# TPA_MONO.net
KiCad netlist of a schematic drawn in Altium Designer
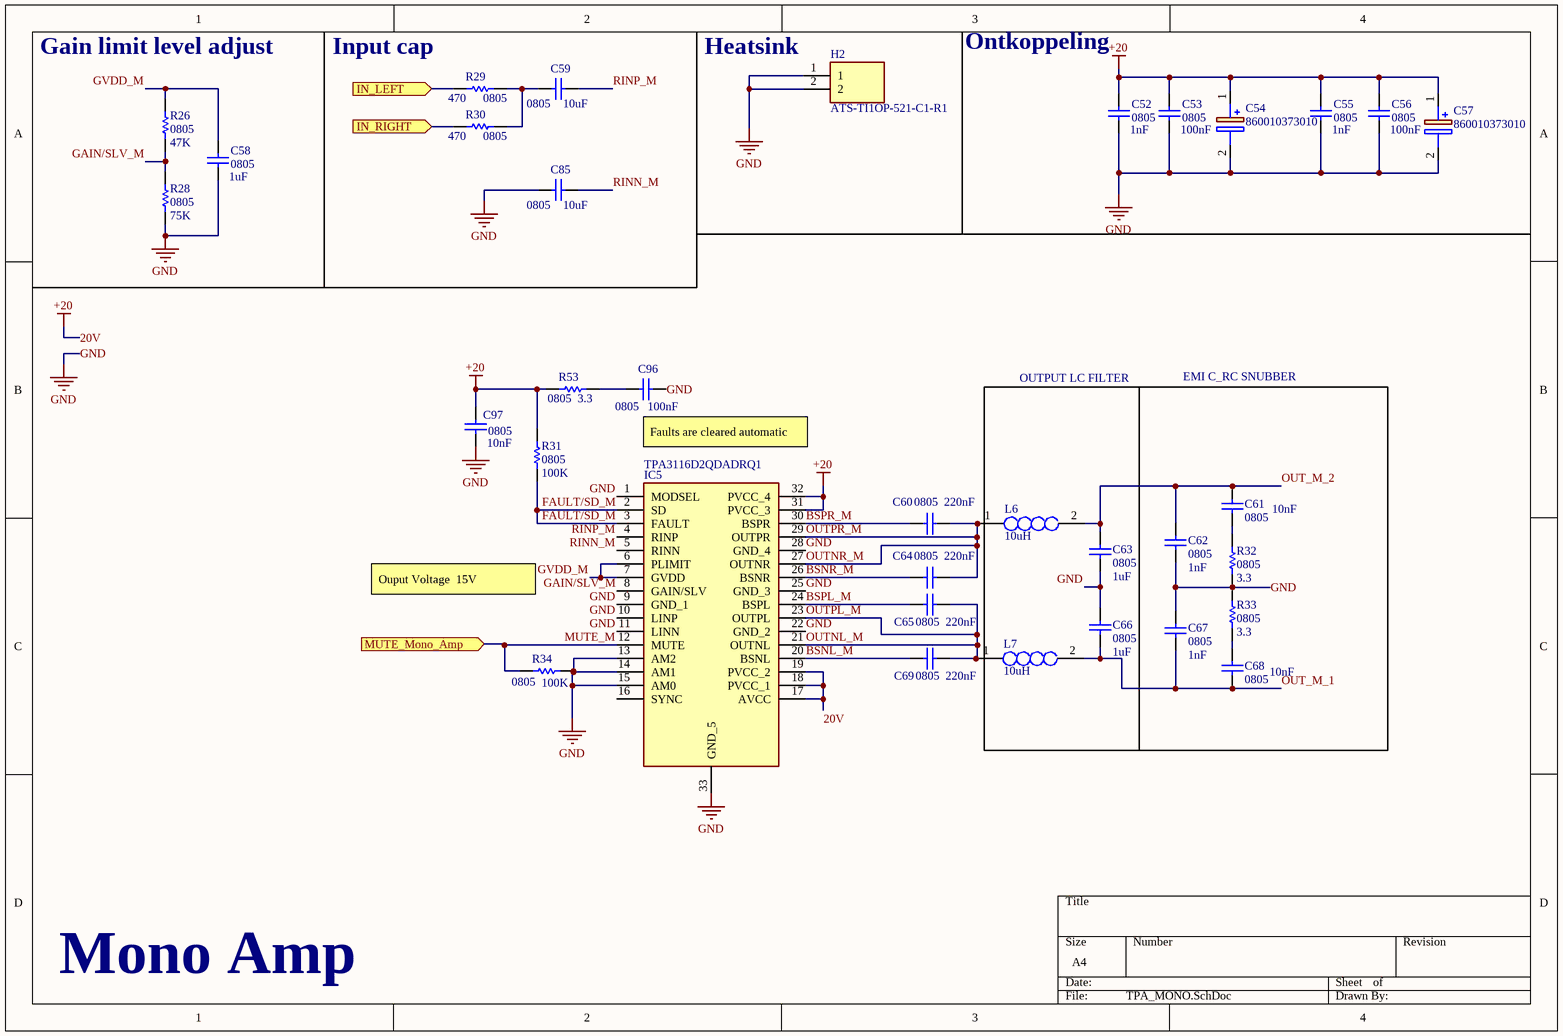
[diagram p0: TPA_MONO.SchDoc]

(export (version "E")
  (design (tool "Eeschema 10.0.6"))
  (components
    (comp (ref "C52")
      (value "0805")
      (footprint "6-0805_N")
      (description "Capacitor")
      (fields (field (name "ALTIUM_VALUE") "1nF") (field (name "PUBLISHER") "Altium Limited"))
      (libsource (lib "Miscellaneous Devices") (part "Cap"))
    )
    (comp (ref "C53")
      (value "0805")
      (footprint "6-0805_N")
      (description "Capacitor")
      (fields (field (name "ALTIUM_VALUE") "100nF") (field (name "PUBLISHER") "Altium Limited"))
      (libsource (lib "Miscellaneous Devices") (part "Cap"))
    )
    (comp (ref "C54")
      (value "860010373010")
      (footprint "SamacSys:CAPPRD250W52D630H1250")
      (description "Capacitor Polarised")
      (fields (field (name "MOUSER PART NUMBER") "710-860010373010"))
      (libsource (lib "*") (part "860010373010"))
    )
    (comp (ref "C55")
      (value "0805")
      (footprint "6-0805_N")
      (description "Capacitor")
      (fields (field (name "ALTIUM_VALUE") "1nF") (field (name "PUBLISHER") "Altium Limited"))
      (libsource (lib "Miscellaneous Devices") (part "Cap"))
    )
    (comp (ref "C56")
      (value "0805")
      (footprint "6-0805_N")
      (description "Capacitor")
      (fields (field (name "ALTIUM_VALUE") "100nF") (field (name "PUBLISHER") "Altium Limited"))
      (libsource (lib "Miscellaneous Devices") (part "Cap"))
    )
    (comp (ref "C57")
      (value "860010373010")
      (footprint "SamacSys:CAPPRD250W52D630H1250")
      (description "Capacitor Polarised")
      (fields (field (name "MOUSER PART NUMBER") "710-860010373010"))
      (libsource (lib "*") (part "860010373010"))
    )
    (comp (ref "C58")
      (value "0805")
      (footprint "6-0805_N")
      (description "Capacitor")
      (fields (field (name "ALTIUM_VALUE") "1uF") (field (name "PUBLISHER") "Altium Limited"))
      (libsource (lib "Miscellaneous Devices") (part "Cap"))
    )
    (comp (ref "C59")
      (value "0805")
      (footprint "6-0805_N")
      (description "Capacitor")
      (fields (field (name "ALTIUM_VALUE") "10uF") (field (name "PUBLISHER") "Altium Limited"))
      (libsource (lib "Miscellaneous Devices") (part "Cap"))
    )
    (comp (ref "C60")
      (value "0805")
      (footprint "6-0805_N")
      (description "Capacitor")
      (fields (field (name "ALTIUM_VALUE") "220nF") (field (name "PUBLISHER") "Altium Limited"))
      (libsource (lib "Miscellaneous Devices") (part "Cap"))
    )
    (comp (ref "C61")
      (value "0805")
      (footprint "6-0805_N")
      (description "Capacitor")
      (fields (field (name "ALTIUM_VALUE") "10nF") (field (name "PUBLISHER") "Altium Limited"))
      (libsource (lib "Miscellaneous Devices") (part "Cap"))
    )
    (comp (ref "C62")
      (value "0805")
      (footprint "6-0805_N")
      (description "Capacitor")
      (fields (field (name "ALTIUM_VALUE") "1nF") (field (name "PUBLISHER") "Altium Limited"))
      (libsource (lib "Miscellaneous Devices") (part "Cap"))
    )
    (comp (ref "C63")
      (value "0805")
      (footprint "6-0805_N")
      (description "Capacitor")
      (fields (field (name "ALTIUM_VALUE") "1uF") (field (name "PUBLISHER") "Altium Limited"))
      (libsource (lib "Miscellaneous Devices") (part "Cap"))
    )
    (comp (ref "C64")
      (value "0805")
      (footprint "6-0805_N")
      (description "Capacitor")
      (fields (field (name "ALTIUM_VALUE") "220nF") (field (name "PUBLISHER") "Altium Limited"))
      (libsource (lib "Miscellaneous Devices") (part "Cap"))
    )
    (comp (ref "C65")
      (value "0805")
      (footprint "6-0805_N")
      (description "Capacitor")
      (fields (field (name "ALTIUM_VALUE") "220nF") (field (name "PUBLISHER") "Altium Limited"))
      (libsource (lib "Miscellaneous Devices") (part "Cap"))
    )
    (comp (ref "C66")
      (value "0805")
      (footprint "6-0805_N")
      (description "Capacitor")
      (fields (field (name "ALTIUM_VALUE") "1uF") (field (name "PUBLISHER") "Altium Limited"))
      (libsource (lib "Miscellaneous Devices") (part "Cap"))
    )
    (comp (ref "C67")
      (value "0805")
      (footprint "6-0805_N")
      (description "Capacitor")
      (fields (field (name "ALTIUM_VALUE") "1nF") (field (name "PUBLISHER") "Altium Limited"))
      (libsource (lib "Miscellaneous Devices") (part "Cap"))
    )
    (comp (ref "C68")
      (value "0805")
      (footprint "6-0805_N")
      (description "Capacitor")
      (fields (field (name "ALTIUM_VALUE") "10nF") (field (name "PUBLISHER") "Altium Limited"))
      (libsource (lib "Miscellaneous Devices") (part "Cap"))
    )
    (comp (ref "C69")
      (value "0805")
      (footprint "6-0805_N")
      (description "Capacitor")
      (fields (field (name "ALTIUM_VALUE") "220nF") (field (name "PUBLISHER") "Altium Limited"))
      (libsource (lib "Miscellaneous Devices") (part "Cap"))
    )
    (comp (ref "C85")
      (value "0805")
      (footprint "6-0805_N")
      (description "Capacitor")
      (fields (field (name "ALTIUM_VALUE") "10uF") (field (name "PUBLISHER") "Altium Limited"))
      (libsource (lib "Miscellaneous Devices") (part "Cap"))
    )
    (comp (ref "C96")
      (value "0805")
      (footprint "6-0805_N")
      (description "Capacitor")
      (fields (field (name "ALTIUM_VALUE") "100nF") (field (name "PUBLISHER") "Altium Limited"))
      (libsource (lib "Miscellaneous Devices") (part "Cap"))
    )
    (comp (ref "C97")
      (value "0805")
      (footprint "6-0805_N")
      (description "Capacitor")
      (fields (field (name "ALTIUM_VALUE") "10nF") (field (name "PUBLISHER") "Altium Limited"))
      (libsource (lib "Miscellaneous Devices") (part "Cap"))
    )
    (comp (ref "H2")
      (value "ATS-TI1OP-521-C1-R1")
      (footprint "SamacSys:ATSTI1OP521C1R1")
      (description "Hardware")
      (fields (field (name "MOUSER PART NUMBER") "984-ATS-TI1OP521C1R1"))
      (libsource (lib "SamacSys") (part "ATS-TI1OP-521-C1-R1"))
    )
    (comp (ref "IC5")
      (value "TPA3116D2QDADRQ1")
      (footprint "SamacSys:SOP65P810X120-33N")
      (description "Integrated Circuit")
      (fields (field (name "MOUSER PART NUMBER") "595-TPA3116D2QDADRQ1"))
      (libsource (lib "SamacSys") (part "TPA3116D2QDADRQ1"))
    )
    (comp (ref "L6")
      (value "10uH")
      (footprint "SamacSys:INDPM110100X400N")
      (description "Inductor")
      (fields
        (field (name "MANUFACTURER_PART_NUMBER") "SRP1038A-4R7M")
        (field (name "MOUSER PART NUMBER") "652-SRP1038A-4R7M")
      )
      (libsource (lib "*") (part "SRP1038A-4R7M"))
    )
    (comp (ref "L7")
      (value "10uH")
      (footprint "SamacSys:INDPM110100X400N")
      (description "Inductor")
      (fields
        (field (name "MANUFACTURER_PART_NUMBER") "SRP1038A-4R7M")
        (field (name "MOUSER PART NUMBER") "652-SRP1038A-4R7M")
      )
      (libsource (lib "*") (part "SRP1038A-4R7M"))
    )
    (comp (ref "R26")
      (value "0805")
      (footprint "6-0805_N")
      (description "Resistor")
      (fields (field (name "ALTIUM_VALUE") "47K") (field (name "PUBLISHER") "Altium Limited"))
      (libsource (lib "Miscellaneous Devices") (part "Res1"))
    )
    (comp (ref "R28")
      (value "0805")
      (footprint "6-0805_N")
      (description "Resistor")
      (fields (field (name "ALTIUM_VALUE") "75K") (field (name "PUBLISHER") "Altium Limited"))
      (libsource (lib "Miscellaneous Devices") (part "Res1"))
    )
    (comp (ref "R29")
      (value "0805")
      (footprint "6-0805_N")
      (description "Resistor")
      (fields (field (name "ALTIUM_VALUE") "470") (field (name "PUBLISHER") "Altium Limited"))
      (libsource (lib "Miscellaneous Devices") (part "Res1"))
    )
    (comp (ref "R30")
      (value "0805")
      (footprint "6-0805_N")
      (description "Resistor")
      (fields (field (name "ALTIUM_VALUE") "470") (field (name "PUBLISHER") "Altium Limited"))
      (libsource (lib "Miscellaneous Devices") (part "Res1"))
    )
    (comp (ref "R31")
      (value "0805")
      (footprint "6-0805_N")
      (description "Resistor")
      (fields (field (name "ALTIUM_VALUE") "100K") (field (name "PUBLISHER") "Altium Limited"))
      (libsource (lib "Miscellaneous Devices") (part "Res1"))
    )
    (comp (ref "R32")
      (value "0805")
      (footprint "6-0805_N")
      (description "Resistor")
      (fields (field (name "ALTIUM_VALUE") "3.3") (field (name "PUBLISHER") "Altium Limited"))
      (libsource (lib "Miscellaneous Devices") (part "Res1"))
    )
    (comp (ref "R33")
      (value "0805")
      (footprint "6-0805_N")
      (description "Resistor")
      (fields (field (name "ALTIUM_VALUE") "3.3") (field (name "PUBLISHER") "Altium Limited"))
      (libsource (lib "Miscellaneous Devices") (part "Res1"))
    )
    (comp (ref "R34")
      (value "0805")
      (footprint "6-0805_N")
      (description "Resistor")
      (fields (field (name "ALTIUM_VALUE") "100K") (field (name "PUBLISHER") "Altium Limited"))
      (libsource (lib "Miscellaneous Devices") (part "Res1"))
    )
    (comp (ref "R53")
      (value "0805")
      (footprint "6-0805_N")
      (description "Resistor")
      (fields (field (name "ALTIUM_VALUE") "3.3") (field (name "PUBLISHER") "Altium Limited"))
      (libsource (lib "Miscellaneous Devices") (part "Res1"))
    )
  )
  (nets
    (net (code "1") (name "+20") (class "Default")
      (node (ref "C52") (pin "1") (pinfunction "1_1") (pintype "passive"))
      (node (ref "C53") (pin "1") (pinfunction "1_1") (pintype "passive"))
      (node (ref "C54") (pin "1") (pinfunction "+_1") (pintype "passive"))
      (node (ref "C55") (pin "1") (pinfunction "1_1") (pintype "passive"))
      (node (ref "C56") (pin "1") (pinfunction "1_1") (pintype "passive"))
      (node (ref "C57") (pin "1") (pinfunction "+_1") (pintype "passive"))
      (node (ref "C97") (pin "1") (pinfunction "1_1") (pintype "passive"))
      (node (ref "IC5") (pin "17") (pinfunction "AVCC_17") (pintype "passive"))
      (node (ref "IC5") (pin "18") (pinfunction "PVCC_1_18") (pintype "passive"))
      (node (ref "IC5") (pin "19") (pinfunction "PVCC_2_19") (pintype "passive"))
      (node (ref "IC5") (pin "31") (pinfunction "PVCC_3_31") (pintype "passive"))
      (node (ref "IC5") (pin "32") (pinfunction "PVCC_4_32") (pintype "passive"))
      (node (ref "R31") (pin "2") (pinfunction "2_2") (pintype "passive"))
      (node (ref "R53") (pin "2") (pinfunction "2_2") (pintype "passive"))
    )
    (net (code "2") (name "/BSNL_M") (class "Default")
      (node (ref "C69") (pin "1") (pinfunction "1_1") (pintype "passive"))
      (node (ref "IC5") (pin "20") (pinfunction "BSNL_20") (pintype "passive"))
    )
    (net (code "3") (name "/BSNR_M") (class "Default")
      (node (ref "C64") (pin "1") (pinfunction "1_1") (pintype "passive"))
      (node (ref "IC5") (pin "26") (pinfunction "BSNR_26") (pintype "passive"))
    )
    (net (code "4") (name "/BSPL_M") (class "Default")
      (node (ref "C65") (pin "1") (pinfunction "1_1") (pintype "passive"))
      (node (ref "IC5") (pin "24") (pinfunction "BSPL_24") (pintype "passive"))
    )
    (net (code "5") (name "/BSPR_M") (class "Default")
      (node (ref "C60") (pin "1") (pinfunction "1_1") (pintype "passive"))
      (node (ref "IC5") (pin "30") (pinfunction "BSPR_30") (pintype "passive"))
    )
    (net (code "6") (name "/FAULT{slash}SD_M") (class "Default")
      (node (ref "IC5") (pin "2") (pinfunction "SD_2") (pintype "passive"))
      (node (ref "IC5") (pin "3") (pinfunction "FAULT_3") (pintype "passive"))
      (node (ref "R31") (pin "1") (pinfunction "1_1") (pintype "passive"))
    )
    (net (code "7") (name "/GAIN{slash}SLV_M") (class "Default")
      (node (ref "IC5") (pin "8") (pinfunction "GAIN/SLV_8") (pintype "passive"))
      (node (ref "R26") (pin "1") (pinfunction "1_1") (pintype "passive"))
      (node (ref "R28") (pin "2") (pinfunction "2_2") (pintype "passive"))
    )
    (net (code "8") (name "/GVDD_M") (class "Default")
      (node (ref "C58") (pin "1") (pinfunction "1_1") (pintype "passive"))
      (node (ref "IC5") (pin "6") (pinfunction "PLIMIT_6") (pintype "passive"))
      (node (ref "IC5") (pin "7") (pinfunction "GVDD_7") (pintype "passive"))
      (node (ref "R26") (pin "2") (pinfunction "2_2") (pintype "passive"))
    )
    (net (code "9") (name "/IN_LEFT") (class "Default")
      (node (ref "R29") (pin "2") (pinfunction "2_2") (pintype "passive"))
    )
    (net (code "10") (name "/IN_RIGHT") (class "Default")
      (node (ref "R30") (pin "2") (pinfunction "2_2") (pintype "passive"))
    )
    (net (code "11") (name "/MUTE_M") (class "Default")
      (node (ref "IC5") (pin "12") (pinfunction "MUTE_12") (pintype "passive"))
      (node (ref "R34") (pin "2") (pinfunction "2_2") (pintype "passive"))
    )
    (net (code "12") (name "/OUTNL_M") (class "Default")
      (node (ref "C65") (pin "2") (pinfunction "2_2") (pintype "passive"))
      (node (ref "C69") (pin "2") (pinfunction "2_2") (pintype "passive"))
      (node (ref "IC5") (pin "21") (pinfunction "OUTNL_21") (pintype "passive"))
      (node (ref "IC5") (pin "23") (pinfunction "OUTPL_23") (pintype "passive"))
      (node (ref "L7") (pin "1") (pinfunction "1_1") (pintype "passive"))
    )
    (net (code "13") (name "/OUTNR_M") (class "Default")
      (node (ref "C60") (pin "2") (pinfunction "2_2") (pintype "passive"))
      (node (ref "C64") (pin "2") (pinfunction "2_2") (pintype "passive"))
      (node (ref "IC5") (pin "27") (pinfunction "OUTNR_27") (pintype "passive"))
      (node (ref "IC5") (pin "29") (pinfunction "OUTPR_29") (pintype "passive"))
      (node (ref "L6") (pin "1") (pinfunction "1_1") (pintype "passive"))
    )
    (net (code "14") (name "/OUT_M_1") (class "Default")
      (node (ref "C66") (pin "1") (pinfunction "1_1") (pintype "passive"))
      (node (ref "C67") (pin "1") (pinfunction "1_1") (pintype "passive"))
      (node (ref "C68") (pin "1") (pinfunction "1_1") (pintype "passive"))
      (node (ref "L7") (pin "2") (pinfunction "2_2") (pintype "passive"))
    )
    (net (code "15") (name "/OUT_M_2") (class "Default")
      (node (ref "C61") (pin "2") (pinfunction "2_2") (pintype "passive"))
      (node (ref "C62") (pin "2") (pinfunction "2_2") (pintype "passive"))
      (node (ref "C63") (pin "2") (pinfunction "2_2") (pintype "passive"))
      (node (ref "L6") (pin "2") (pinfunction "2_2") (pintype "passive"))
    )
    (net (code "16") (name "/RINN_M") (class "Default")
      (node (ref "C85") (pin "2") (pinfunction "2_2") (pintype "passive"))
      (node (ref "IC5") (pin "5") (pinfunction "RINN_5") (pintype "passive"))
    )
    (net (code "17") (name "/RINP_M") (class "Default")
      (node (ref "C59") (pin "2") (pinfunction "2_2") (pintype "passive"))
      (node (ref "IC5") (pin "4") (pinfunction "RINP_4") (pintype "passive"))
    )
    (net (code "18") (name "GND") (class "Default")
      (node (ref "C52") (pin "2") (pinfunction "2_2") (pintype "passive"))
      (node (ref "C53") (pin "2") (pinfunction "2_2") (pintype "passive"))
      (node (ref "C54") (pin "2") (pinfunction "-_2") (pintype "passive"))
      (node (ref "C55") (pin "2") (pinfunction "2_2") (pintype "passive"))
      (node (ref "C56") (pin "2") (pinfunction "2_2") (pintype "passive"))
      (node (ref "C57") (pin "2") (pinfunction "-_2") (pintype "passive"))
      (node (ref "C58") (pin "2") (pinfunction "2_2") (pintype "passive"))
      (node (ref "C62") (pin "1") (pinfunction "1_1") (pintype "passive"))
      (node (ref "C63") (pin "1") (pinfunction "1_1") (pintype "passive"))
      (node (ref "C66") (pin "2") (pinfunction "2_2") (pintype "passive"))
      (node (ref "C67") (pin "2") (pinfunction "2_2") (pintype "passive"))
      (node (ref "C85") (pin "1") (pinfunction "1_1") (pintype "passive"))
      (node (ref "C96") (pin "2") (pinfunction "2_2") (pintype "passive"))
      (node (ref "C97") (pin "2") (pinfunction "2_2") (pintype "passive"))
      (node (ref "H2") (pin "1") (pinfunction "1_1") (pintype "passive"))
      (node (ref "H2") (pin "2") (pinfunction "2_2") (pintype "passive"))
      (node (ref "IC5") (pin "1") (pinfunction "MODSEL_1") (pintype "passive"))
      (node (ref "IC5") (pin "10") (pinfunction "LINP_10") (pintype "passive"))
      (node (ref "IC5") (pin "11") (pinfunction "LINN_11") (pintype "passive"))
      (node (ref "IC5") (pin "13") (pinfunction "AM2_13") (pintype "passive"))
      (node (ref "IC5") (pin "14") (pinfunction "AM1_14") (pintype "passive"))
      (node (ref "IC5") (pin "15") (pinfunction "AM0_15") (pintype "passive"))
      (node (ref "IC5") (pin "22") (pinfunction "GND_2_22") (pintype "passive"))
      (node (ref "IC5") (pin "25") (pinfunction "GND_3_25") (pintype "passive"))
      (node (ref "IC5") (pin "28") (pinfunction "GND_4_28") (pintype "passive"))
      (node (ref "IC5") (pin "33") (pinfunction "GND_5_33") (pintype "passive"))
      (node (ref "IC5") (pin "9") (pinfunction "GND_1_9") (pintype "passive"))
      (node (ref "R28") (pin "1") (pinfunction "1_1") (pintype "passive"))
      (node (ref "R32") (pin "1") (pinfunction "1_1") (pintype "passive"))
      (node (ref "R33") (pin "2") (pinfunction "2_2") (pintype "passive"))
      (node (ref "R34") (pin "1") (pinfunction "1_1") (pintype "passive"))
    )
    (net (code "19") (name "Net-(C59-Pad1)") (class "Default")
      (node (ref "C59") (pin "1") (pinfunction "1_1") (pintype "passive"))
      (node (ref "R29") (pin "1") (pinfunction "1_1") (pintype "passive"))
      (node (ref "R30") (pin "1") (pinfunction "1_1") (pintype "passive"))
    )
    (net (code "20") (name "Net-(C61-Pad1)") (class "Default")
      (node (ref "C61") (pin "1") (pinfunction "1_1") (pintype "passive"))
      (node (ref "R32") (pin "2") (pinfunction "2_2") (pintype "passive"))
    )
    (net (code "21") (name "Net-(C68-Pad2)") (class "Default")
      (node (ref "C68") (pin "2") (pinfunction "2_2") (pintype "passive"))
      (node (ref "R33") (pin "1") (pinfunction "1_1") (pintype "passive"))
    )
    (net (code "22") (name "Net-(C96-Pad1)") (class "Default")
      (node (ref "C96") (pin "1") (pinfunction "1_1") (pintype "passive"))
      (node (ref "R53") (pin "1") (pinfunction "1_1") (pintype "passive"))
    )
    (net (code "23") (name "unconnected-(IC5-SYNC-Pad16)") (class "Default")
      (node (ref "IC5") (pin "16") (pinfunction "SYNC_16") (pintype "passive"))
    )
  )
)
